# Analog_Channel.net
KiCad netlist of a schematic drawn in Altium Designer
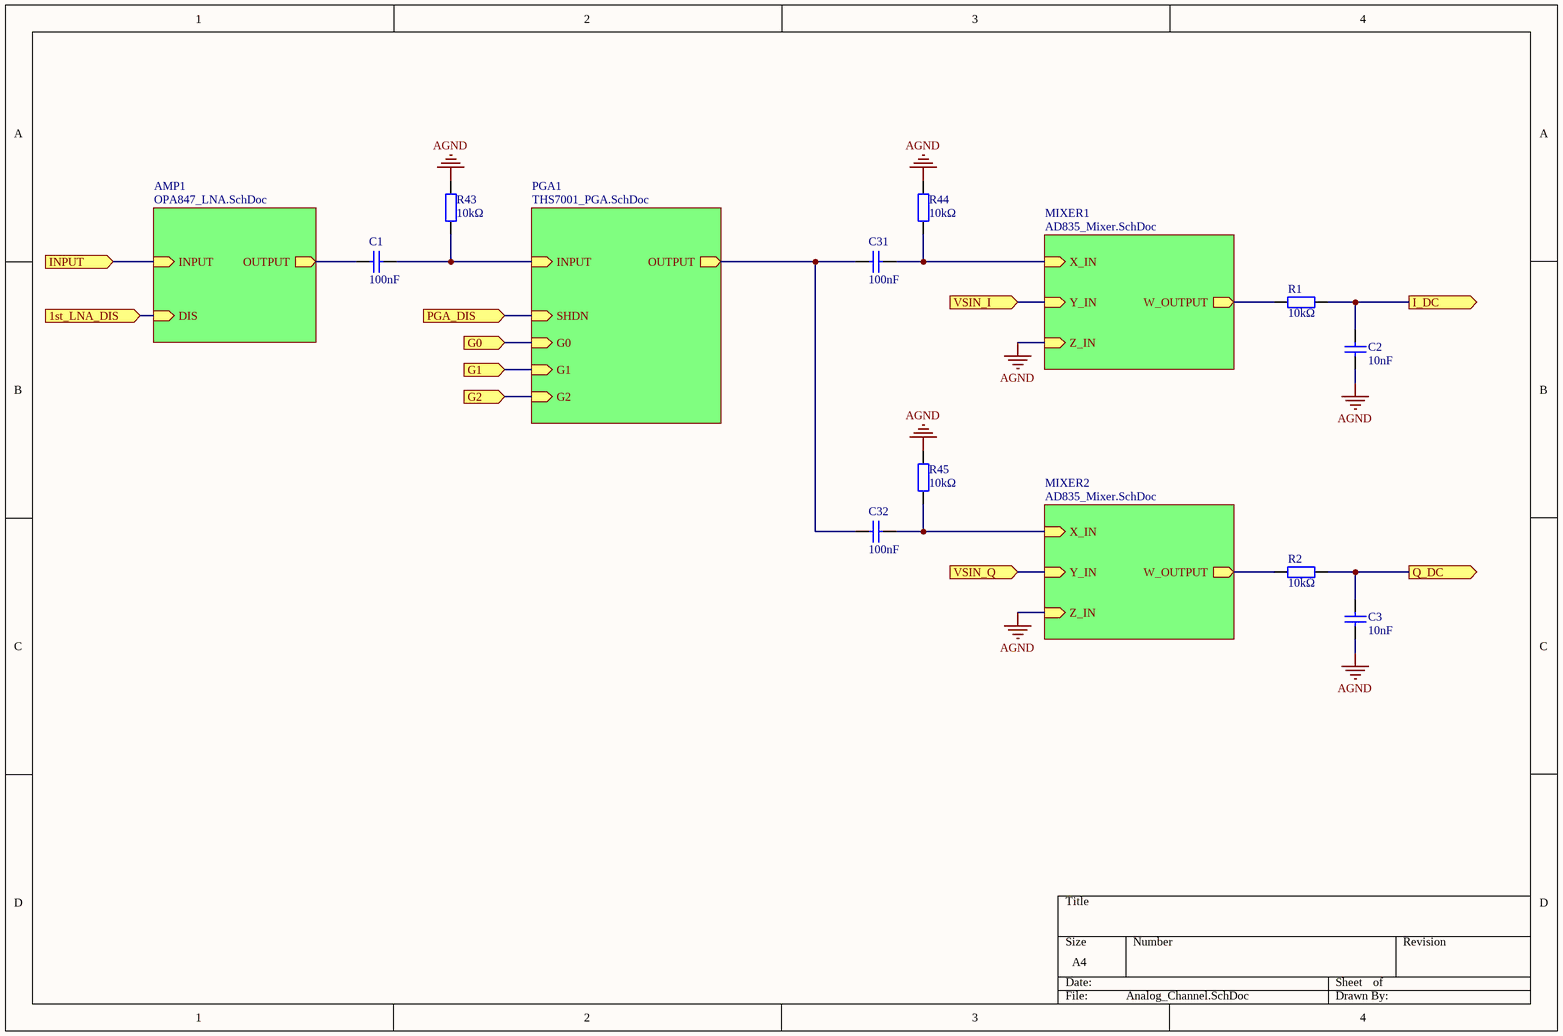
[diagram p0: Analog_Channel.SchDoc]

(export (version "E")
  (design (tool "Eeschema 10.0.6"))
  (components
    (comp (ref "C1")
      (value "100nF")
      (footprint "0805_C")
      (description "贴片电容")
      (libsource (lib "Miscellaneous Devices LC") (part "0805 100nF(104) 10% 50V"))
    )
    (comp (ref "C2")
      (value "10nF")
      (footprint "0603_C")
      (description "贴片电容")
      (libsource (lib "Miscellaneous Devices LC") (part "0603 10nF (103) 10% 50V"))
    )
    (comp (ref "C3")
      (value "10nF")
      (footprint "0603_C")
      (description "贴片电容")
      (libsource (lib "Miscellaneous Devices LC") (part "0603 10nF (103) 10% 50V"))
    )
    (comp (ref "C31")
      (value "100nF")
      (footprint "0805_C")
      (description "贴片电容")
      (libsource (lib "Miscellaneous Devices LC") (part "0805 100nF(104) 10% 50V"))
    )
    (comp (ref "C32")
      (value "100nF")
      (footprint "0805_C")
      (description "贴片电容")
      (libsource (lib "Miscellaneous Devices LC") (part "0805 100nF(104) 10% 50V"))
    )
    (comp (ref "R1")
      (value "10kΩ")
      (footprint "0603_R")
      (description "贴片电阻")
      (libsource (lib "") (part "0603 10KΩ (1002) 1%_1"))
    )
    (comp (ref "R2")
      (value "10kΩ")
      (footprint "0603_R")
      (description "贴片电阻")
      (libsource (lib "") (part "0603 10KΩ (1002) 1%_1"))
    )
    (comp (ref "R43")
      (value "10kΩ")
      (footprint "0603_R")
      (description "贴片电阻")
      (libsource (lib "Miscellaneous Devices LC") (part "0603 10KΩ (1002) 1%"))
    )
    (comp (ref "R44")
      (value "10kΩ")
      (footprint "0603_R")
      (description "贴片电阻")
      (libsource (lib "Miscellaneous Devices LC") (part "0603 10KΩ (1002) 1%"))
    )
    (comp (ref "R45")
      (value "10kΩ")
      (footprint "0603_R")
      (description "贴片电阻")
      (libsource (lib "Miscellaneous Devices LC") (part "0603 10KΩ (1002) 1%"))
    )
  )
  (nets
    (net (code "6") (name "/INPUT_1") (class "Default")
      (node (ref "C1") (pin "2") (pinfunction "2_2") (pintype "passive"))
      (node (ref "R43") (pin "2") (pinfunction "2_2") (pintype "passive"))
    )
    (net (code "7") (name "/I_DC") (class "Default")
      (node (ref "C2") (pin "2") (pinfunction "2_2") (pintype "passive"))
      (node (ref "R1") (pin "1") (pinfunction "1_1") (pintype "passive"))
    )
    (net (code "8") (name "/OUTPUT") (class "Default")
      (node (ref "C1") (pin "1") (pinfunction "1_1") (pintype "passive"))
    )
    (net (code "9") (name "/OUTPUT_1") (class "Default")
      (node (ref "C31") (pin "1") (pinfunction "1_1") (pintype "passive"))
      (node (ref "C32") (pin "1") (pinfunction "1_1") (pintype "passive"))
    )
    (net (code "11") (name "/Q_DC") (class "Default")
      (node (ref "C3") (pin "2") (pinfunction "2_2") (pintype "passive"))
      (node (ref "R2") (pin "1") (pinfunction "1_1") (pintype "passive"))
    )
    (net (code "14") (name "/W_OUTPUT") (class "Default")
      (node (ref "R2") (pin "2") (pinfunction "2_2") (pintype "passive"))
    )
    (net (code "15") (name "/W_OUTPUT_1") (class "Default")
      (node (ref "R1") (pin "2") (pinfunction "2_2") (pintype "passive"))
    )
    (net (code "16") (name "/X_IN") (class "Default")
      (node (ref "C31") (pin "2") (pinfunction "2_2") (pintype "passive"))
      (node (ref "R44") (pin "2") (pinfunction "2_2") (pintype "passive"))
    )
    (net (code "17") (name "/X_IN_1") (class "Default")
      (node (ref "C32") (pin "2") (pinfunction "2_2") (pintype "passive"))
      (node (ref "R45") (pin "2") (pinfunction "2_2") (pintype "passive"))
    )
    (net (code "18") (name "AGND") (class "Default")
      (node (ref "C2") (pin "1") (pinfunction "1_1") (pintype "passive"))
      (node (ref "C3") (pin "1") (pinfunction "1_1") (pintype "passive"))
      (node (ref "R43") (pin "1") (pinfunction "1_1") (pintype "passive"))
      (node (ref "R44") (pin "1") (pinfunction "1_1") (pintype "passive"))
      (node (ref "R45") (pin "1") (pinfunction "1_1") (pintype "passive"))
    )
  )
)
